# CON_SD_SDAMB-012.net
KiCad netlist of a schematic drawn in Altium Designer
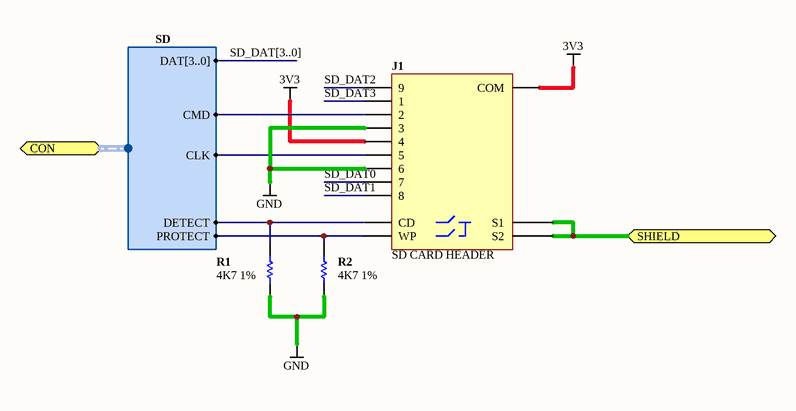
[diagram p0: CON_SD_SDAMB-012.SchDoc]

(export (version "E")
  (design (tool "Eeschema 10.0.6"))
  (components
    (comp (ref "J1")
      (value "SD CARD HEADER")
      (footprint "SDAMB-012")
      (description "SD Card Connector, Type A without Cover; Surface Mount; 9-Position")
      (libsource (lib "AltiumDesignLibrary") (part "SDAMB-012"))
    )
    (comp (ref "R1")
      (value "4K7 1%")
      (footprint "RESC1005-STAR")
      (description "Resistor, 4K7 1% 0402 (1005)")
      (fields (field (name "TOLERANCE") "1 %"))
      (libsource (lib "altium-import") (part "root_2_RES_"))
    )
    (comp (ref "R2")
      (value "4K7 1%")
      (footprint "RESC1005-STAR")
      (description "Resistor, 4K7 1% 0402 (1005)")
      (fields (field (name "TOLERANCE") "1 %"))
      (libsource (lib "altium-import") (part "root_2_RES_"))
    )
  )
  (nets
    (net (code "2") (name "/CLK") (class "Default")
      (node (ref "J1") (pin "5") (pinfunction "5_5") (pintype "passive"))
    )
    (net (code "3") (name "/CMD") (class "Default")
      (node (ref "J1") (pin "2") (pinfunction "2_2") (pintype "passive"))
    )
    (net (code "5") (name "/DETECT") (class "Default")
      (node (ref "J1") (pin "CD") (pinfunction "CD_CD") (pintype "passive"))
      (node (ref "R1") (pin "2") (pinfunction "2_2") (pintype "passive"))
    )
    (net (code "6") (name "/PROTECT") (class "Default")
      (node (ref "J1") (pin "WP") (pinfunction "WP_WP") (pintype "passive"))
      (node (ref "R2") (pin "2") (pinfunction "2_2") (pintype "passive"))
    )
    (net (code "7") (name "/SD_DAT0") (class "Default")
      (node (ref "J1") (pin "7") (pinfunction "7_7") (pintype "passive"))
    )
    (net (code "8") (name "/SD_DAT1") (class "Default")
      (node (ref "J1") (pin "8") (pinfunction "8_8") (pintype "passive"))
    )
    (net (code "9") (name "/SD_DAT2") (class "Default")
      (node (ref "J1") (pin "9") (pinfunction "9_9") (pintype "passive"))
    )
    (net (code "10") (name "/SD_DAT3") (class "Default")
      (node (ref "J1") (pin "1") (pinfunction "1_1") (pintype "passive"))
    )
    (net (code "11") (name "/SHIELD") (class "Default")
      (node (ref "J1") (pin "S1") (pinfunction "S1_S1") (pintype "passive"))
      (node (ref "J1") (pin "S2") (pinfunction "S2_S2") (pintype "passive"))
    )
    (net (code "13") (name "3V3") (class "Default")
      (node (ref "J1") (pin "4") (pinfunction "4_4") (pintype "passive"))
      (node (ref "J1") (pin "COM") (pinfunction "COM_COM") (pintype "passive"))
    )
    (net (code "14") (name "GND") (class "Default")
      (node (ref "J1") (pin "3") (pinfunction "3_3") (pintype "passive"))
      (node (ref "J1") (pin "6") (pinfunction "6_6") (pintype "passive"))
      (node (ref "R1") (pin "1") (pinfunction "1_1") (pintype "passive"))
      (node (ref "R2") (pin "1") (pinfunction "1_1") (pintype "passive"))
    )
  )
)
